# sem8700.net
KiCad netlist of a schematic drawn in Altium Designer
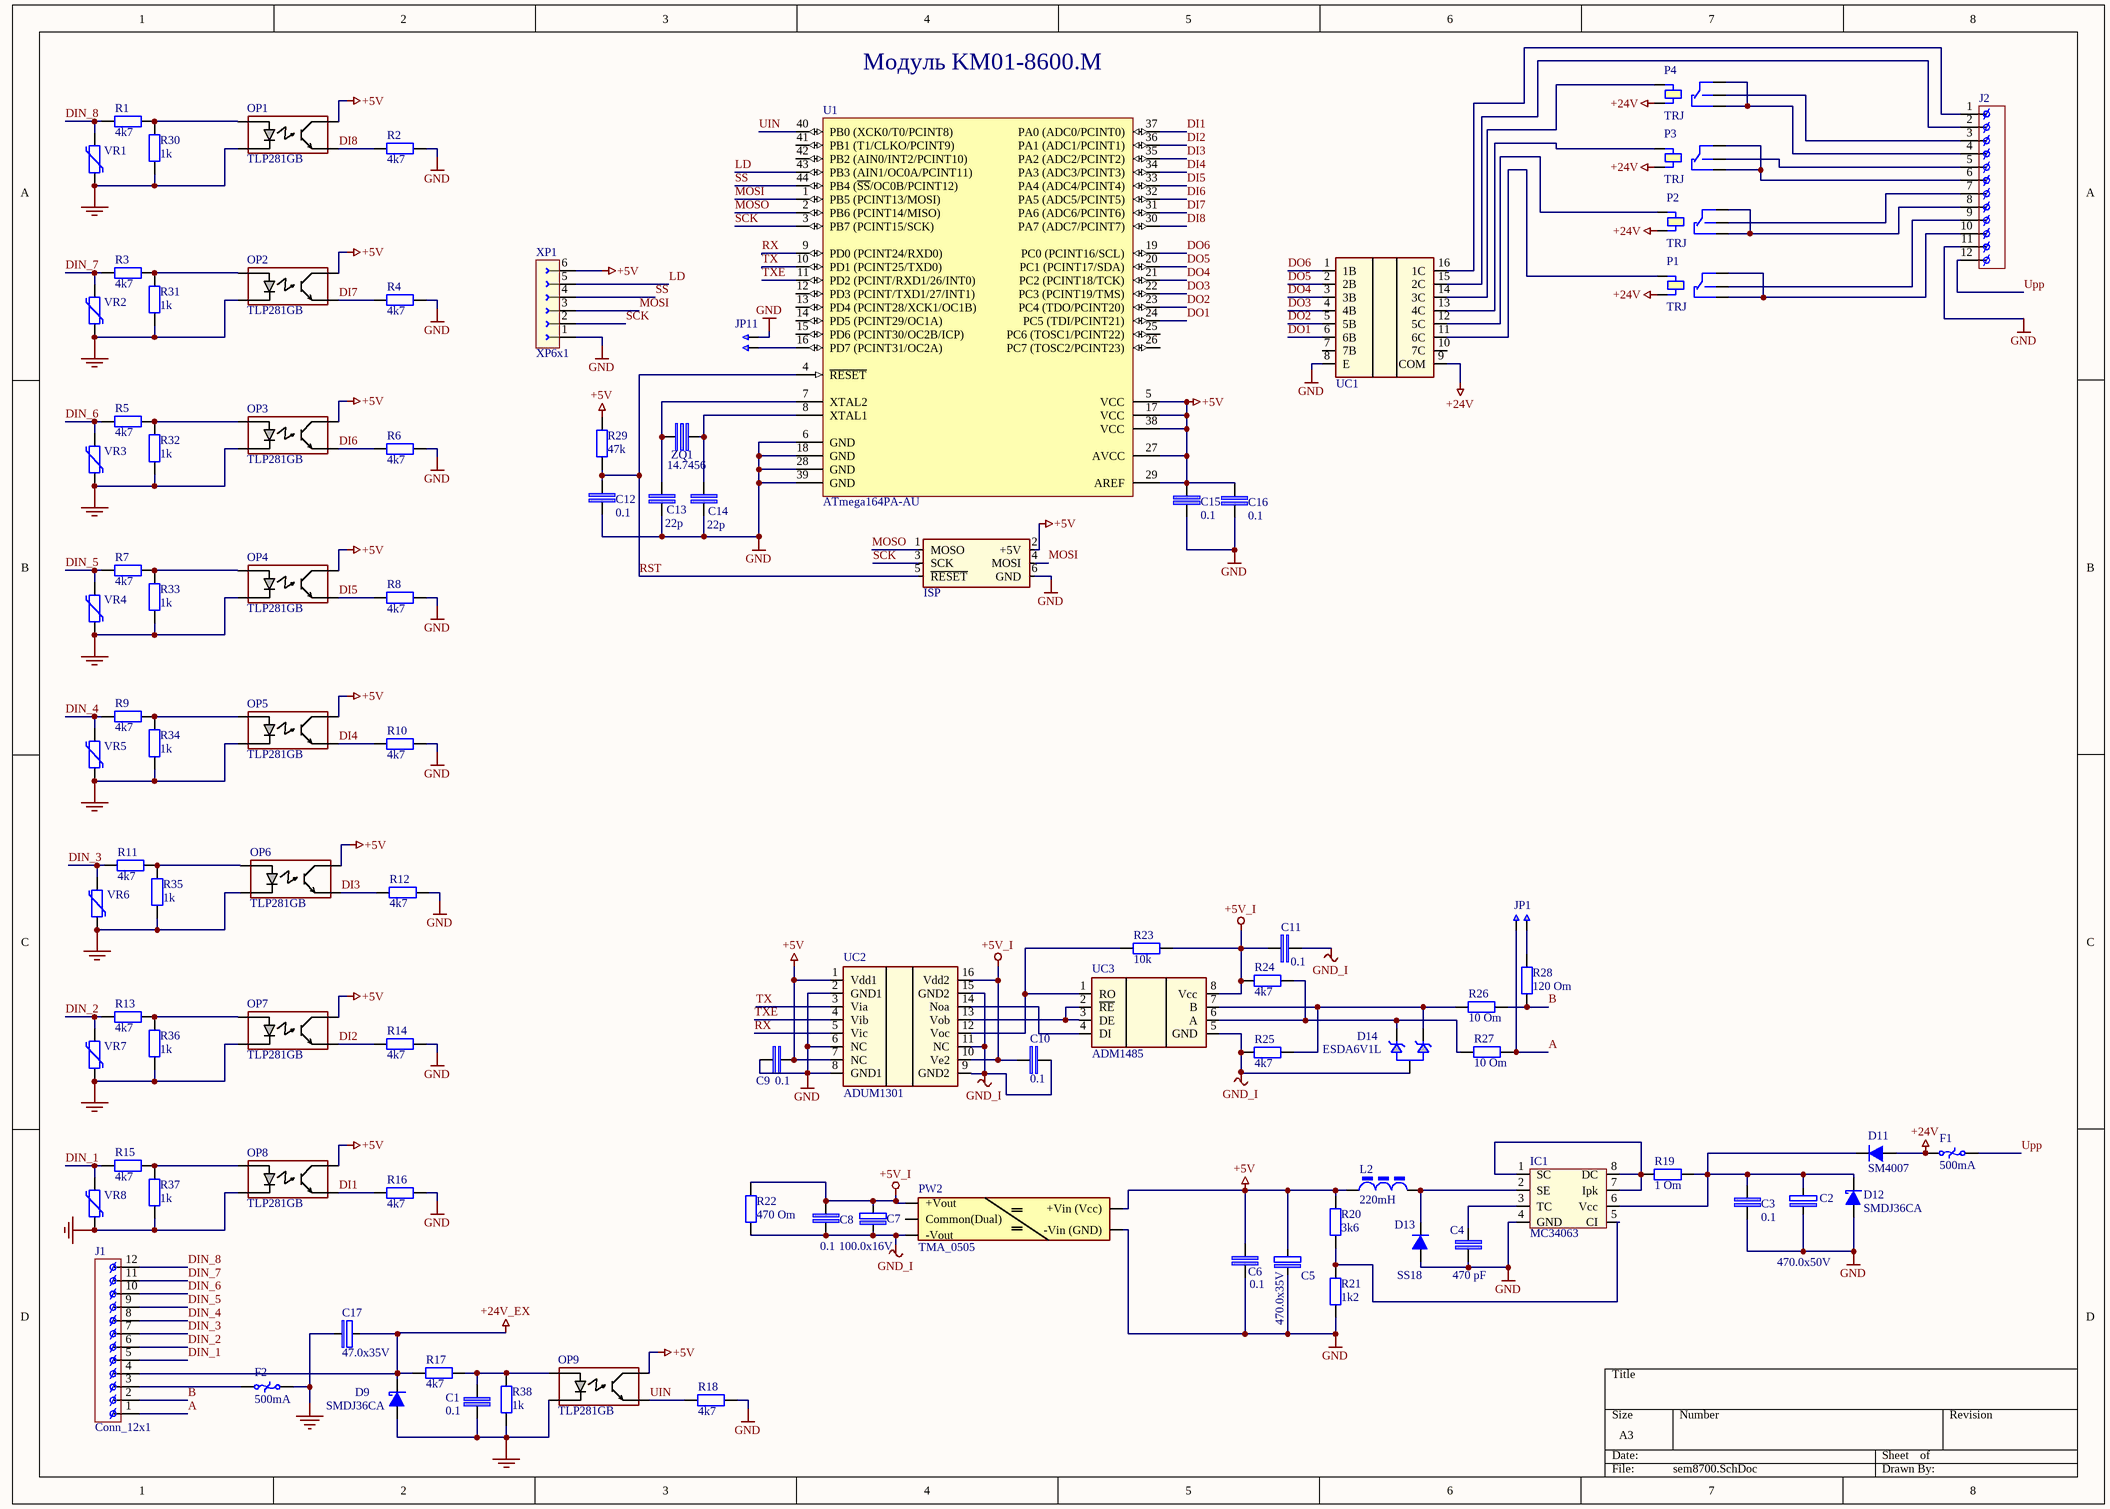
[diagram p0: sem8700.SchDoc]

(export (version "E")
  (design (tool "Eeschema 10.0.6"))
  (components
    (comp (ref "C1") (value "0.1") (footprint "CAPC2113X13N_0805") (libsource (lib "Lib_my1") (part "cap_1")))
    (comp (ref "C2")
      (value "470.0x50V")
      (footprint "Cap_pol_13x25")
      (libsource (lib "Lib_my1") (part "Cap_pol1"))
    )
    (comp (ref "C3") (value "0.1") (footprint "CAPC2113X13N_0805") (libsource (lib "Lib_my1") (part "cap_1")))
    (comp (ref "C4")
      (value "470 pF")
      (footprint "CAPC2113X13N_0805")
      (libsource (lib "Lib_my1") (part "cap_1"))
    )
    (comp (ref "C5")
      (value "470.0x35V")
      (footprint "Cap_2(10x12.5)")
      (libsource (lib "Lib_my1") (part "Cap_pol2"))
    )
    (comp (ref "C6") (value "0.1") (footprint "CAPC2113X13N_0805") (libsource (lib "Lib_my1") (part "cap_1")))
    (comp (ref "C7") (value "100.0x16V") (footprint "Cap_4(5x10)") (libsource (lib "") (part "Cap_pol2_1")))
    (comp (ref "C8") (value "0.1") (footprint "CAPC2113X13N_0805") (libsource (lib "") (part "cap_1_1")))
    (comp (ref "C9") (value "0.1") (footprint "CAPC2113X13N_0805") (libsource (lib "") (part "cap_1_1")))
    (comp (ref "C10") (value "0.1") (footprint "CAPC2113X13N_0805") (libsource (lib "") (part "cap_1_2")))
    (comp (ref "C11") (value "0.1") (footprint "CAPC2113X13N_0805") (libsource (lib "") (part "cap_1_1")))
    (comp (ref "C12")
      (value "0.1")
      (footprint "CAPC2113X13N_0805")
      (libsource (lib "Lib_my1") (part "cap_1"))
    )
    (comp (ref "C13")
      (value "22p")
      (footprint "CAPC2113X13N_0805")
      (libsource (lib "Lib_my1") (part "cap_1"))
    )
    (comp (ref "C14")
      (value "22p")
      (footprint "CAPC2113X13N_0805")
      (libsource (lib "Lib_my1") (part "cap_1"))
    )
    (comp (ref "C15")
      (value "0.1")
      (footprint "CAPC2113X13N_0805")
      (libsource (lib "Lib_my1") (part "cap_1"))
    )
    (comp (ref "C16")
      (value "0.1")
      (footprint "CAPC2113X13N_0805")
      (libsource (lib "Lib_my1") (part "cap_1"))
    )
    (comp (ref "C17")
      (value "47.0x35V")
      (footprint "Cap_4(5x10)")
      (libsource (lib "Lib_my1") (part "Cap_pol2"))
    )
    (comp (ref "D9") (value "SMDJ36CA") (footprint "SMB_1") (libsource (lib "Lib_my1") (part "Diodes_SMB")))
    (comp (ref "D11")
      (value "SM4007")
      (footprint "DIOD_SM1")
      (libsource (lib "Lib_my1") (part "Diodes_4007"))
    )
    (comp (ref "D12") (value "SMDJ36CA") (footprint "SMB_1") (libsource (lib "Lib_my1") (part "Diodes_SMB")))
    (comp (ref "D13") (value "SS18") (footprint "DIOD_SMA") (libsource (lib "Lib_my1") (part "Diod_30BQ100")))
    (comp (ref "D14")
      (value "ESDA6V1L")
      (footprint "SOT23_diod_ESDA")
      (libsource (lib "Lib_my1") (part "Diod_ESDA"))
    )
    (comp (ref "F1") (value "500mA") (footprint "Fuse_termo") (libsource (lib "Lib_my1") (part "Fuse_term")))
    (comp (ref "F2") (value "500mA") (footprint "Fuse_termo") (libsource (lib "Lib_my1") (part "Fuse_term")))
    (comp (ref "IC1")
      (value "MC34063")
      (footprint "SOIC_SO-8")
      (libsource (lib "Lib_my1") (part "MC34063_1"))
    )
    (comp (ref "ISP") (value "ISP") (footprint "ISP_1") (libsource (lib "Lib_my1") (part "ISP_1")))
    (comp (ref "J1") (value "Conn_12x1") (footprint "conn12_2") (libsource (lib "") (part "Conn_12x1_1")))
    (comp (ref "J2")
      (value "Conn_12x1")
      (footprint "conn12_2")
      (libsource (lib "Lib_my1") (part "Conn_12x1"))
    )
    (comp (ref "JP1") (value "jamper") (footprint "JP_2_2.5") (libsource (lib "Lib_my1") (part "JP_2x2.5")))
    (comp (ref "JP11") (value "jamper") (footprint "JP_2_2.5") (libsource (lib "Lib_my1") (part "JP_2x2.5")))
    (comp (ref "L2") (value "220mH") (footprint "Dr_1") (libsource (lib "Lib_my1") (part "Dr_1")))
    (comp (ref "OP1")
      (value "TLP281GB")
      (footprint "SOIC127_TPL")
      (libsource (lib "Lib_my1") (part "opto_TLP"))
    )
    (comp (ref "OP2")
      (value "TLP281GB")
      (footprint "SOIC127_TPL")
      (libsource (lib "Lib_my1") (part "opto_TLP"))
    )
    (comp (ref "OP3")
      (value "TLP281GB")
      (footprint "SOIC127_TPL")
      (libsource (lib "Lib_my1") (part "opto_TLP"))
    )
    (comp (ref "OP4")
      (value "TLP281GB")
      (footprint "SOIC127_TPL")
      (libsource (lib "Lib_my1") (part "opto_TLP"))
    )
    (comp (ref "OP5")
      (value "TLP281GB")
      (footprint "SOIC127_TPL")
      (libsource (lib "Lib_my1") (part "opto_TLP"))
    )
    (comp (ref "OP6")
      (value "TLP281GB")
      (footprint "SOIC127_TPL")
      (libsource (lib "Lib_my1") (part "opto_TLP"))
    )
    (comp (ref "OP7")
      (value "TLP281GB")
      (footprint "SOIC127_TPL")
      (libsource (lib "Lib_my1") (part "opto_TLP"))
    )
    (comp (ref "OP8")
      (value "TLP281GB")
      (footprint "SOIC127_TPL")
      (libsource (lib "Lib_my1") (part "opto_TLP"))
    )
    (comp (ref "OP9")
      (value "TLP281GB")
      (footprint "SOIC127_TPL")
      (libsource (lib "Lib_my1") (part "opto_TLP"))
    )
    (comp (ref "P1") (value "TRJ") (footprint "PCB_RELE_TRJ1") (libsource (lib "Lib_my1") (part "Rele_TRJ")))
    (comp (ref "P2") (value "TRJ") (footprint "PCB_RELE_TRJ1") (libsource (lib "Lib_my1") (part "Rele_TRJ")))
    (comp (ref "P3") (value "TRJ") (footprint "PCB_RELE_TRJ1") (libsource (lib "Lib_my1") (part "Rele_TRJ")))
    (comp (ref "P4") (value "TRJ") (footprint "PCB_RELE_TRJ1") (libsource (lib "Lib_my1") (part "Rele_TRJ")))
    (comp (ref "PW2")
      (value "TMA_0505")
      (footprint "TMA_1W_new")
      (libsource (lib "Lib_my1") (part "TRACO_PW1"))
    )
    (comp (ref "R1") (value "4k7") (footprint "RES_1206") (libsource (lib "") (part "rez_1_1")))
    (comp (ref "R2") (value "4k7") (footprint "RESC2113X0805N") (libsource (lib "") (part "rez_1_1")))
    (comp (ref "R3") (value "4k7") (footprint "RES_1206") (libsource (lib "") (part "rez_1_1")))
    (comp (ref "R4") (value "4k7") (footprint "RESC2113X0805N") (libsource (lib "") (part "rez_1_1")))
    (comp (ref "R5") (value "4k7") (footprint "RES_1206") (libsource (lib "") (part "rez_1_1")))
    (comp (ref "R6") (value "4k7") (footprint "RESC2113X0805N") (libsource (lib "") (part "rez_1_1")))
    (comp (ref "R7") (value "4k7") (footprint "RES_1206") (libsource (lib "") (part "rez_1_1")))
    (comp (ref "R8") (value "4k7") (footprint "RESC2113X0805N") (libsource (lib "") (part "rez_1_1")))
    (comp (ref "R9") (value "4k7") (footprint "RES_1206") (libsource (lib "") (part "rez_1_1")))
    (comp (ref "R10") (value "4k7") (footprint "RESC2113X0805N") (libsource (lib "") (part "rez_1_1")))
    (comp (ref "R11") (value "4k7") (footprint "RES_1206") (libsource (lib "") (part "rez_1_1")))
    (comp (ref "R12") (value "4k7") (footprint "RESC2113X0805N") (libsource (lib "") (part "rez_1_1")))
    (comp (ref "R13") (value "4k7") (footprint "RES_1206") (libsource (lib "") (part "rez_1_1")))
    (comp (ref "R14") (value "4k7") (footprint "RESC2113X0805N") (libsource (lib "") (part "rez_1_1")))
    (comp (ref "R15") (value "4k7") (footprint "RES_1206") (libsource (lib "") (part "rez_1_1")))
    (comp (ref "R16") (value "4k7") (footprint "RESC2113X0805N") (libsource (lib "") (part "rez_1_1")))
    (comp (ref "R17") (value "4k7") (footprint "RES_1206") (libsource (lib "") (part "rez_1_1")))
    (comp (ref "R18") (value "4k7") (footprint "RESC2113X0805N") (libsource (lib "") (part "rez_1_1")))
    (comp (ref "R19") (value "1 Om") (footprint "RES_1206") (libsource (lib "") (part "rez_1_1")))
    (comp (ref "R20") (value "3k6") (footprint "RESC2113X0805N") (libsource (lib "Lib_my1") (part "rez_1")))
    (comp (ref "R21") (value "1k2") (footprint "RESC2113X0805N") (libsource (lib "Lib_my1") (part "rez_1")))
    (comp (ref "R22") (value "470 Om") (footprint "RES_1206") (libsource (lib "") (part "rez_1_3")))
    (comp (ref "R23") (value "10k") (footprint "RESC2113X0805N") (libsource (lib "") (part "rez_1_3")))
    (comp (ref "R24") (value "4k7") (footprint "RESC2113X0805N") (libsource (lib "") (part "rez_1_3")))
    (comp (ref "R25") (value "4k7") (footprint "RESC2113X0805N") (libsource (lib "") (part "rez_1_3")))
    (comp (ref "R26") (value "10 Om") (footprint "RESC2113X0805N") (libsource (lib "") (part "rez_1_3")))
    (comp (ref "R27") (value "10 Om") (footprint "RESC2113X0805N") (libsource (lib "") (part "rez_1_3")))
    (comp (ref "R28") (value "120 Om") (footprint "RES_1206") (libsource (lib "Lib_my1") (part "rez_1")))
    (comp (ref "R29") (value "47k") (footprint "RESC2113X0805N") (libsource (lib "Lib_my1") (part "rez_1")))
    (comp (ref "R30") (value "1k") (footprint "RESC2113X0805N") (libsource (lib "") (part "rez_1_2")))
    (comp (ref "R31") (value "1k") (footprint "RESC2113X0805N") (libsource (lib "Lib_my1") (part "rez_1")))
    (comp (ref "R32") (value "1k") (footprint "RESC2113X0805N") (libsource (lib "Lib_my1") (part "rez_1")))
    (comp (ref "R33") (value "1k") (footprint "RESC2113X0805N") (libsource (lib "Lib_my1") (part "rez_1")))
    (comp (ref "R34") (value "1k") (footprint "RESC2113X0805N") (libsource (lib "Lib_my1") (part "rez_1")))
    (comp (ref "R35") (value "1k") (footprint "RESC2113X0805N") (libsource (lib "Lib_my1") (part "rez_1")))
    (comp (ref "R36") (value "1k") (footprint "RESC2113X0805N") (libsource (lib "Lib_my1") (part "rez_1")))
    (comp (ref "R37") (value "1k") (footprint "RESC2113X0805N") (libsource (lib "Lib_my1") (part "rez_1")))
    (comp (ref "R38") (value "1k") (footprint "RESC2113X0805N") (libsource (lib "Lib_my1") (part "rez_1")))
    (comp (ref "U1")
      (value "ATmega164PA-AU")
      (footprint "44A_N")
      (fields (field (name "PUBLISHER") "Altium Limited"))
      (libsource (lib "Atmel Microcontroller 8-Bit megaAVR") (part "ATmega164PA-AU"))
    )
    (comp (ref "UC1") (value "ULN2003A") (footprint "PDIP16_1") (libsource (lib "Lib_my1") (part "ULN2003A")))
    (comp (ref "UC2")
      (value "ADUM1301")
      (footprint "SOIC127P1030X265-16N_SOIC_W")
      (libsource (lib "Lib_my1") (part "ADUM1301"))
    )
    (comp (ref "UC3")
      (value "ADM1485")
      (footprint "SOIC127P600X175-8N_SOIC_SO8")
      (libsource (lib "Lib_my1") (part "ADM485"))
    )
    (comp (ref "VR1") (value "CN1206K25G") (footprint "var1206") (libsource (lib "") (part "var_smd1_1")))
    (comp (ref "VR2")
      (value "CN1206K25G")
      (footprint "var1206")
      (libsource (lib "Lib_my1") (part "var_smd1"))
    )
    (comp (ref "VR3")
      (value "CN1206K25G")
      (footprint "var1206")
      (libsource (lib "Lib_my1") (part "var_smd1"))
    )
    (comp (ref "VR4")
      (value "CN1206K25G")
      (footprint "var1206")
      (libsource (lib "Lib_my1") (part "var_smd1"))
    )
    (comp (ref "VR5")
      (value "CN1206K25G")
      (footprint "var1206")
      (libsource (lib "Lib_my1") (part "var_smd1"))
    )
    (comp (ref "VR6")
      (value "CN1206K25G")
      (footprint "var1206")
      (libsource (lib "Lib_my1") (part "var_smd1"))
    )
    (comp (ref "VR7")
      (value "CN1206K25G")
      (footprint "var1206")
      (libsource (lib "Lib_my1") (part "var_smd1"))
    )
    (comp (ref "VR8")
      (value "CN1206K25G")
      (footprint "var1206")
      (libsource (lib "Lib_my1") (part "var_smd1"))
    )
    (comp (ref "XP1") (value "XP6x1") (footprint "CONN_WF-6") (libsource (lib "Lib_my1") (part "Connect6_1")))
    (comp (ref "ZQ1") (value "14.7456") (footprint "ZQ_1") (libsource (lib "Lib_my1") (part "ZQ_1")))
  )
  (nets
    (net (code "1") (name "+5V") (class "Default")
      (node (ref "C15") (pin "1") (pinfunction "1_1") (pintype "passive"))
      (node (ref "C16") (pin "1") (pinfunction "1_1") (pintype "passive"))
      (node (ref "C5") (pin "1") (pinfunction "1_1") (pintype "passive"))
      (node (ref "C6") (pin "1") (pinfunction "1_1") (pintype "passive"))
      (node (ref "C9") (pin "1") (pinfunction "1_1") (pintype "passive"))
      (node (ref "ISP") (pin "2") (pinfunction "+5V_2") (pintype "passive"))
      (node (ref "L2") (pin "2") (pinfunction "2_2") (pintype "passive"))
      (node (ref "OP1") (pin "4") (pinfunction "4_4") (pintype "passive"))
      (node (ref "OP2") (pin "4") (pinfunction "4_4") (pintype "passive"))
      (node (ref "OP3") (pin "4") (pinfunction "4_4") (pintype "passive"))
      (node (ref "OP4") (pin "4") (pinfunction "4_4") (pintype "passive"))
      (node (ref "OP5") (pin "4") (pinfunction "4_4") (pintype "passive"))
      (node (ref "OP6") (pin "4") (pinfunction "4_4") (pintype "passive"))
      (node (ref "OP7") (pin "4") (pinfunction "4_4") (pintype "passive"))
      (node (ref "OP8") (pin "4") (pinfunction "4_4") (pintype "passive"))
      (node (ref "OP9") (pin "4") (pinfunction "4_4") (pintype "passive"))
      (node (ref "PW2") (pin "1") (pinfunction "+Vin_(Vcc)_1") (pintype "passive"))
      (node (ref "R20") (pin "2") (pinfunction "2_2") (pintype "passive"))
      (node (ref "R29") (pin "2") (pinfunction "2_2") (pintype "passive"))
      (node (ref "U1") (pin "17") (pinfunction "VCC_17") (pintype "power_in"))
      (node (ref "U1") (pin "27") (pinfunction "AVCC_27") (pintype "power_in"))
      (node (ref "U1") (pin "29") (pinfunction "AREF_29") (pintype "power_in"))
      (node (ref "U1") (pin "38") (pinfunction "VCC_38") (pintype "power_in"))
      (node (ref "U1") (pin "5") (pinfunction "VCC_5") (pintype "power_in"))
      (node (ref "UC2") (pin "1") (pinfunction "Vdd1_1") (pintype "passive"))
      (node (ref "UC2") (pin "7") (pinfunction "NC_7") (pintype "passive"))
      (node (ref "XP1") (pin "6") (pinfunction "6_6") (pintype "passive"))
    )
    (net (code "2") (name "+5V_I") (class "Default")
      (node (ref "C10") (pin "1") (pinfunction "1_1") (pintype "passive"))
      (node (ref "C11") (pin "2") (pinfunction "2_2") (pintype "passive"))
      (node (ref "C7") (pin "1") (pinfunction "1_1") (pintype "passive"))
      (node (ref "C8") (pin "1") (pinfunction "1_1") (pintype "passive"))
      (node (ref "PW2") (pin "5") (pinfunction "+Vout_5") (pintype "passive"))
      (node (ref "R22") (pin "1") (pinfunction "1_1") (pintype "passive"))
      (node (ref "R23") (pin "1") (pinfunction "1_1") (pintype "passive"))
      (node (ref "R24") (pin "2") (pinfunction "2_2") (pintype "passive"))
      (node (ref "UC2") (pin "10") (pinfunction "Ve2_10") (pintype "passive"))
      (node (ref "UC2") (pin "16") (pinfunction "Vdd2_16") (pintype "passive"))
      (node (ref "UC3") (pin "8") (pinfunction "Vcc_8") (pintype "passive"))
    )
    (net (code "3") (name "+24V") (class "Default")
      (node (ref "D11") (pin "1") (pinfunction "1_1") (pintype "passive"))
      (node (ref "F1") (pin "1") (pinfunction "1_1") (pintype "passive"))
      (node (ref "P1") (pin "5") (pinfunction "5_5") (pintype "passive"))
      (node (ref "P2") (pin "5") (pinfunction "5_5") (pintype "passive"))
      (node (ref "P3") (pin "5") (pinfunction "5_5") (pintype "passive"))
      (node (ref "P4") (pin "5") (pinfunction "5_5") (pintype "passive"))
      (node (ref "UC1") (pin "9") (pinfunction "COM_9") (pintype "passive"))
    )
    (net (code "4") (name "+24V_EX") (class "Default")
      (node (ref "C17") (pin "1") (pinfunction "1_1") (pintype "passive"))
      (node (ref "D9") (pin "1") (pinfunction "1_1") (pintype "passive"))
      (node (ref "J1") (pin "4") (pinfunction "4_4") (pintype "passive"))
      (node (ref "R17") (pin "1") (pinfunction "1_1") (pintype "passive"))
    )
    (net (code "5") (name "/A") (class "Default")
      (node (ref "J1") (pin "1") (pinfunction "1_1") (pintype "passive"))
      (node (ref "JP1") (pin "1") (pinfunction "1_1") (pintype "passive"))
      (node (ref "R27") (pin "1") (pinfunction "1_1") (pintype "passive"))
    )
    (net (code "6") (name "/B") (class "Default")
      (node (ref "J1") (pin "2") (pinfunction "2_2") (pintype "passive"))
      (node (ref "R26") (pin "1") (pinfunction "1_1") (pintype "passive"))
      (node (ref "R28") (pin "1") (pinfunction "1_1") (pintype "passive"))
    )
    (net (code "7") (name "/DI1") (class "Default")
      (node (ref "OP8") (pin "3") (pinfunction "3_3") (pintype "passive"))
      (node (ref "R16") (pin "1") (pinfunction "1_1") (pintype "passive"))
      (node (ref "U1") (pin "37") (pinfunction "PA0_(ADC0/PCINT0)_37") (pintype "bidirectional"))
    )
    (net (code "8") (name "/DI2") (class "Default")
      (node (ref "OP7") (pin "3") (pinfunction "3_3") (pintype "passive"))
      (node (ref "R14") (pin "1") (pinfunction "1_1") (pintype "passive"))
      (node (ref "U1") (pin "36") (pinfunction "PA1_(ADC1/PCINT1)_36") (pintype "bidirectional"))
    )
    (net (code "9") (name "/DI3") (class "Default")
      (node (ref "OP6") (pin "3") (pinfunction "3_3") (pintype "passive"))
      (node (ref "R12") (pin "1") (pinfunction "1_1") (pintype "passive"))
      (node (ref "U1") (pin "35") (pinfunction "PA2_(ADC2/PCINT2)_35") (pintype "bidirectional"))
    )
    (net (code "10") (name "/DI4") (class "Default")
      (node (ref "OP5") (pin "3") (pinfunction "3_3") (pintype "passive"))
      (node (ref "R10") (pin "1") (pinfunction "1_1") (pintype "passive"))
      (node (ref "U1") (pin "34") (pinfunction "PA3_(ADC3/PCINT3)_34") (pintype "bidirectional"))
    )
    (net (code "11") (name "/DI5") (class "Default")
      (node (ref "OP4") (pin "3") (pinfunction "3_3") (pintype "passive"))
      (node (ref "R8") (pin "1") (pinfunction "1_1") (pintype "passive"))
      (node (ref "U1") (pin "33") (pinfunction "PA4_(ADC4/PCINT4)_33") (pintype "bidirectional"))
    )
    (net (code "12") (name "/DI6") (class "Default")
      (node (ref "OP3") (pin "3") (pinfunction "3_3") (pintype "passive"))
      (node (ref "R6") (pin "1") (pinfunction "1_1") (pintype "passive"))
      (node (ref "U1") (pin "32") (pinfunction "PA5_(ADC5/PCINT5)_32") (pintype "bidirectional"))
    )
    (net (code "13") (name "/DI7") (class "Default")
      (node (ref "OP2") (pin "3") (pinfunction "3_3") (pintype "passive"))
      (node (ref "R4") (pin "1") (pinfunction "1_1") (pintype "passive"))
      (node (ref "U1") (pin "31") (pinfunction "PA6_(ADC6/PCINT6)_31") (pintype "bidirectional"))
    )
    (net (code "14") (name "/DI8") (class "Default")
      (node (ref "OP1") (pin "3") (pinfunction "3_3") (pintype "passive"))
      (node (ref "R2") (pin "1") (pinfunction "1_1") (pintype "passive"))
      (node (ref "U1") (pin "30") (pinfunction "PA7_(ADC7/PCINT7)_30") (pintype "bidirectional"))
    )
    (net (code "15") (name "/DIN_1") (class "Default")
      (node (ref "J1") (pin "5") (pinfunction "5_5") (pintype "passive"))
      (node (ref "R15") (pin "1") (pinfunction "1_1") (pintype "passive"))
      (node (ref "VR8") (pin "2") (pinfunction "2_2") (pintype "passive"))
    )
    (net (code "16") (name "/DIN_2") (class "Default")
      (node (ref "J1") (pin "6") (pinfunction "6_6") (pintype "passive"))
      (node (ref "R13") (pin "1") (pinfunction "1_1") (pintype "passive"))
      (node (ref "VR7") (pin "2") (pinfunction "2_2") (pintype "passive"))
    )
    (net (code "17") (name "/DIN_3") (class "Default")
      (node (ref "J1") (pin "7") (pinfunction "7_7") (pintype "passive"))
      (node (ref "R11") (pin "1") (pinfunction "1_1") (pintype "passive"))
      (node (ref "VR6") (pin "2") (pinfunction "2_2") (pintype "passive"))
    )
    (net (code "18") (name "/DIN_4") (class "Default")
      (node (ref "J1") (pin "8") (pinfunction "8_8") (pintype "passive"))
      (node (ref "R9") (pin "1") (pinfunction "1_1") (pintype "passive"))
      (node (ref "VR5") (pin "2") (pinfunction "2_2") (pintype "passive"))
    )
    (net (code "19") (name "/DIN_5") (class "Default")
      (node (ref "J1") (pin "9") (pinfunction "9_9") (pintype "passive"))
      (node (ref "R7") (pin "1") (pinfunction "1_1") (pintype "passive"))
      (node (ref "VR4") (pin "2") (pinfunction "2_2") (pintype "passive"))
    )
    (net (code "20") (name "/DIN_6") (class "Default")
      (node (ref "J1") (pin "10") (pinfunction "10_10") (pintype "passive"))
      (node (ref "R5") (pin "1") (pinfunction "1_1") (pintype "passive"))
      (node (ref "VR3") (pin "2") (pinfunction "2_2") (pintype "passive"))
    )
    (net (code "21") (name "/DIN_7") (class "Default")
      (node (ref "J1") (pin "11") (pinfunction "11_11") (pintype "passive"))
      (node (ref "R3") (pin "1") (pinfunction "1_1") (pintype "passive"))
      (node (ref "VR2") (pin "2") (pinfunction "2_2") (pintype "passive"))
    )
    (net (code "22") (name "/DIN_8") (class "Default")
      (node (ref "J1") (pin "12") (pinfunction "12_12") (pintype "passive"))
      (node (ref "R1") (pin "1") (pinfunction "1_1") (pintype "passive"))
      (node (ref "VR1") (pin "2") (pinfunction "2_2") (pintype "passive"))
    )
    (net (code "23") (name "/DO1") (class "Default")
      (node (ref "U1") (pin "24") (pinfunction "PC5_(TDI/PCINT21)_24") (pintype "bidirectional"))
      (node (ref "UC1") (pin "6") (pinfunction "6B_6") (pintype "passive"))
    )
    (net (code "24") (name "/DO2") (class "Default")
      (node (ref "U1") (pin "23") (pinfunction "PC4_(TDO/PCINT20)_23") (pintype "bidirectional"))
      (node (ref "UC1") (pin "5") (pinfunction "5B_5") (pintype "passive"))
    )
    (net (code "25") (name "/DO3") (class "Default")
      (node (ref "U1") (pin "22") (pinfunction "PC3_(PCINT19/TMS)_22") (pintype "bidirectional"))
      (node (ref "UC1") (pin "4") (pinfunction "4B_4") (pintype "passive"))
    )
    (net (code "26") (name "/DO4") (class "Default")
      (node (ref "U1") (pin "21") (pinfunction "PC2_(PCINT18/TCK)_21") (pintype "bidirectional"))
      (node (ref "UC1") (pin "3") (pinfunction "3B_3") (pintype "passive"))
    )
    (net (code "27") (name "/DO5") (class "Default")
      (node (ref "U1") (pin "20") (pinfunction "PC1_(PCINT17/SDA)_20") (pintype "bidirectional"))
      (node (ref "UC1") (pin "2") (pinfunction "2B_2") (pintype "passive"))
    )
    (net (code "28") (name "/DO6") (class "Default")
      (node (ref "U1") (pin "19") (pinfunction "PC0_(PCINT16/SCL)_19") (pintype "bidirectional"))
      (node (ref "UC1") (pin "1") (pinfunction "1B_1") (pintype "passive"))
    )
    (net (code "29") (name "/LD") (class "Default")
      (node (ref "U1") (pin "43") (pinfunction "PB3_(AIN1/OC0A/PCINT11)_43") (pintype "bidirectional"))
      (node (ref "XP1") (pin "5") (pinfunction "5_5") (pintype "passive"))
    )
    (net (code "30") (name "/MOSI") (class "Default")
      (node (ref "ISP") (pin "4") (pinfunction "MOSI_4") (pintype "passive"))
      (node (ref "U1") (pin "1") (pinfunction "PB5_(PCINT13/MOSI)_1") (pintype "bidirectional"))
      (node (ref "XP1") (pin "3") (pinfunction "3_3") (pintype "passive"))
    )
    (net (code "31") (name "/MOSO") (class "Default")
      (node (ref "ISP") (pin "1") (pinfunction "MOSO_1") (pintype "passive"))
      (node (ref "U1") (pin "2") (pinfunction "PB6_(PCINT14/MISO)_2") (pintype "bidirectional"))
    )
    (net (code "32") (name "/RST") (class "Default")
      (node (ref "C12") (pin "1") (pinfunction "1_1") (pintype "passive"))
      (node (ref "ISP") (pin "5") (pinfunction "~{RESET}_5") (pintype "passive"))
      (node (ref "R29") (pin "1") (pinfunction "1_1") (pintype "passive"))
      (node (ref "U1") (pin "4") (pinfunction "~{RESET}_4") (pintype "input"))
    )
    (net (code "33") (name "/RX") (class "Default")
      (node (ref "U1") (pin "9") (pinfunction "PD0_(PCINT24/RXD0)_9") (pintype "bidirectional"))
      (node (ref "UC2") (pin "5") (pinfunction "Vic_5") (pintype "passive"))
    )
    (net (code "34") (name "/SCK") (class "Default")
      (node (ref "ISP") (pin "3") (pinfunction "SCK_3") (pintype "passive"))
      (node (ref "U1") (pin "3") (pinfunction "PB7_(PCINT15/SCK)_3") (pintype "bidirectional"))
      (node (ref "XP1") (pin "2") (pinfunction "2_2") (pintype "passive"))
    )
    (net (code "35") (name "/SS") (class "Default")
      (node (ref "U1") (pin "44") (pinfunction "PB4_(~{SS}/OC0B/PCINT12)_44") (pintype "bidirectional"))
      (node (ref "XP1") (pin "4") (pinfunction "4_4") (pintype "passive"))
    )
    (net (code "36") (name "/TX") (class "Default")
      (node (ref "U1") (pin "10") (pinfunction "PD1_(PCINT25/TXD0)_10") (pintype "bidirectional"))
      (node (ref "UC2") (pin "3") (pinfunction "Via_3") (pintype "passive"))
    )
    (net (code "37") (name "/TXE") (class "Default")
      (node (ref "U1") (pin "11") (pinfunction "PD2_(PCINT/RXD1/26/INT0)_11") (pintype "bidirectional"))
      (node (ref "UC2") (pin "4") (pinfunction "Vib_4") (pintype "passive"))
    )
    (net (code "38") (name "/UIN") (class "Default")
      (node (ref "OP9") (pin "3") (pinfunction "3_3") (pintype "passive"))
      (node (ref "R18") (pin "1") (pinfunction "1_1") (pintype "passive"))
      (node (ref "U1") (pin "40") (pinfunction "PB0_(XCK0/T0/PCINT8)_40") (pintype "bidirectional"))
    )
    (net (code "39") (name "/Upp") (class "Default")
      (node (ref "F1") (pin "2") (pinfunction "2_2") (pintype "passive"))
      (node (ref "J2") (pin "12") (pinfunction "12_12") (pintype "passive"))
    )
    (net (code "40") (name "GND") (class "Default")
      (node (ref "C12") (pin "2") (pinfunction "2_2") (pintype "passive"))
      (node (ref "C13") (pin "2") (pinfunction "2_2") (pintype "passive"))
      (node (ref "C14") (pin "2") (pinfunction "2_2") (pintype "passive"))
      (node (ref "C15") (pin "2") (pinfunction "2_2") (pintype "passive"))
      (node (ref "C16") (pin "2") (pinfunction "2_2") (pintype "passive"))
      (node (ref "C2") (pin "2") (pinfunction "2_2") (pintype "passive"))
      (node (ref "C3") (pin "2") (pinfunction "2_2") (pintype "passive"))
      (node (ref "C4") (pin "2") (pinfunction "2_2") (pintype "passive"))
      (node (ref "C5") (pin "2") (pinfunction "2_2") (pintype "passive"))
      (node (ref "C6") (pin "2") (pinfunction "2_2") (pintype "passive"))
      (node (ref "C9") (pin "2") (pinfunction "2_2") (pintype "passive"))
      (node (ref "D12") (pin "2") (pinfunction "2_2") (pintype "passive"))
      (node (ref "D13") (pin "1") (pinfunction "1_1") (pintype "passive"))
      (node (ref "IC1") (pin "4") (pinfunction "GND_4") (pintype "passive"))
      (node (ref "ISP") (pin "6") (pinfunction "GND_6") (pintype "passive"))
      (node (ref "J2") (pin "11") (pinfunction "11_11") (pintype "passive"))
      (node (ref "JP11") (pin "2") (pinfunction "2_2") (pintype "passive"))
      (node (ref "PW2") (pin "2") (pinfunction "-Vin_(GND)_2") (pintype "passive"))
      (node (ref "R10") (pin "2") (pinfunction "2_2") (pintype "passive"))
      (node (ref "R12") (pin "2") (pinfunction "2_2") (pintype "passive"))
      (node (ref "R14") (pin "2") (pinfunction "2_2") (pintype "passive"))
      (node (ref "R16") (pin "2") (pinfunction "2_2") (pintype "passive"))
      (node (ref "R18") (pin "2") (pinfunction "2_2") (pintype "passive"))
      (node (ref "R2") (pin "2") (pinfunction "2_2") (pintype "passive"))
      (node (ref "R21") (pin "1") (pinfunction "1_1") (pintype "passive"))
      (node (ref "R4") (pin "2") (pinfunction "2_2") (pintype "passive"))
      (node (ref "R6") (pin "2") (pinfunction "2_2") (pintype "passive"))
      (node (ref "R8") (pin "2") (pinfunction "2_2") (pintype "passive"))
      (node (ref "U1") (pin "18") (pinfunction "GND_18") (pintype "power_in"))
      (node (ref "U1") (pin "28") (pinfunction "GND_28") (pintype "power_in"))
      (node (ref "U1") (pin "39") (pinfunction "GND_39") (pintype "power_in"))
      (node (ref "U1") (pin "6") (pinfunction "GND_6") (pintype "power_in"))
      (node (ref "UC1") (pin "8") (pinfunction "E_8") (pintype "passive"))
      (node (ref "UC2") (pin "2") (pinfunction "GND1_2") (pintype "passive"))
      (node (ref "UC2") (pin "6") (pinfunction "NC_6") (pintype "passive"))
      (node (ref "UC2") (pin "8") (pinfunction "GND1_8") (pintype "passive"))
      (node (ref "XP1") (pin "1") (pinfunction "1_1") (pintype "passive"))
    )
    (net (code "41") (name "GND_EX") (class "Default")
      (node (ref "C1") (pin "2") (pinfunction "2_2") (pintype "passive"))
      (node (ref "C17") (pin "2") (pinfunction "2_2") (pintype "passive"))
      (node (ref "D9") (pin "2") (pinfunction "2_2") (pintype "passive"))
      (node (ref "F2") (pin "2") (pinfunction "2_2") (pintype "passive"))
      (node (ref "OP1") (pin "2") (pinfunction "2_2") (pintype "passive"))
      (node (ref "OP2") (pin "2") (pinfunction "2_2") (pintype "passive"))
      (node (ref "OP3") (pin "2") (pinfunction "2_2") (pintype "passive"))
      (node (ref "OP4") (pin "2") (pinfunction "2_2") (pintype "passive"))
      (node (ref "OP5") (pin "2") (pinfunction "2_2") (pintype "passive"))
      (node (ref "OP6") (pin "2") (pinfunction "2_2") (pintype "passive"))
      (node (ref "OP7") (pin "2") (pinfunction "2_2") (pintype "passive"))
      (node (ref "OP8") (pin "2") (pinfunction "2_2") (pintype "passive"))
      (node (ref "OP9") (pin "2") (pinfunction "2_2") (pintype "passive"))
      (node (ref "R30") (pin "1") (pinfunction "1_1") (pintype "passive"))
      (node (ref "R31") (pin "1") (pinfunction "1_1") (pintype "passive"))
      (node (ref "R32") (pin "1") (pinfunction "1_1") (pintype "passive"))
      (node (ref "R33") (pin "1") (pinfunction "1_1") (pintype "passive"))
      (node (ref "R34") (pin "1") (pinfunction "1_1") (pintype "passive"))
      (node (ref "R35") (pin "1") (pinfunction "1_1") (pintype "passive"))
      (node (ref "R36") (pin "1") (pinfunction "1_1") (pintype "passive"))
      (node (ref "R37") (pin "1") (pinfunction "1_1") (pintype "passive"))
      (node (ref "R38") (pin "1") (pinfunction "1_1") (pintype "passive"))
      (node (ref "VR1") (pin "1") (pinfunction "1_1") (pintype "passive"))
      (node (ref "VR2") (pin "1") (pinfunction "1_1") (pintype "passive"))
      (node (ref "VR3") (pin "1") (pinfunction "1_1") (pintype "passive"))
      (node (ref "VR4") (pin "1") (pinfunction "1_1") (pintype "passive"))
      (node (ref "VR5") (pin "1") (pinfunction "1_1") (pintype "passive"))
      (node (ref "VR6") (pin "1") (pinfunction "1_1") (pintype "passive"))
      (node (ref "VR7") (pin "1") (pinfunction "1_1") (pintype "passive"))
      (node (ref "VR8") (pin "1") (pinfunction "1_1") (pintype "passive"))
    )
    (net (code "42") (name "GND_I") (class "Default")
      (node (ref "C10") (pin "2") (pinfunction "2_2") (pintype "passive"))
      (node (ref "C11") (pin "1") (pinfunction "1_1") (pintype "passive"))
      (node (ref "C7") (pin "2") (pinfunction "2_2") (pintype "passive"))
      (node (ref "C8") (pin "2") (pinfunction "2_2") (pintype "passive"))
      (node (ref "D14") (pin "3") (pinfunction "3_3") (pintype "passive"))
      (node (ref "PW2") (pin "3") (pinfunction "-Vout_3") (pintype "passive"))
      (node (ref "R22") (pin "2") (pinfunction "2_2") (pintype "passive"))
      (node (ref "R25") (pin "2") (pinfunction "2_2") (pintype "passive"))
      (node (ref "UC2") (pin "11") (pinfunction "NC_11") (pintype "passive"))
      (node (ref "UC2") (pin "15") (pinfunction "GND2_15") (pintype "passive"))
      (node (ref "UC2") (pin "9") (pinfunction "GND2_9") (pintype "passive"))
      (node (ref "UC3") (pin "5") (pinfunction "GND_5") (pintype "passive"))
    )
    (net (code "43") (name "Net-(C1-Pad1)") (class "Default")
      (node (ref "C1") (pin "1") (pinfunction "1_1") (pintype "passive"))
      (node (ref "OP9") (pin "1") (pinfunction "1_1") (pintype "passive"))
      (node (ref "R17") (pin "2") (pinfunction "2_2") (pintype "passive"))
      (node (ref "R38") (pin "2") (pinfunction "2_2") (pintype "passive"))
    )
    (net (code "44") (name "Net-(F2-Pad1)") (class "Default")
      (node (ref "F2") (pin "1") (pinfunction "1_1") (pintype "passive"))
      (node (ref "J1") (pin "3") (pinfunction "3_3") (pintype "passive"))
    )
    (net (code "45") (name "Net-(IC1-CI)") (class "Default")
      (node (ref "IC1") (pin "5") (pinfunction "CI_5") (pintype "passive"))
      (node (ref "R20") (pin "1") (pinfunction "1_1") (pintype "passive"))
      (node (ref "R21") (pin "2") (pinfunction "2_2") (pintype "passive"))
    )
    (net (code "46") (name "Net-(IC1-DC)") (class "Default")
      (node (ref "IC1") (pin "1") (pinfunction "SC_1") (pintype "passive"))
      (node (ref "IC1") (pin "7") (pinfunction "Ipk_7") (pintype "passive"))
      (node (ref "IC1") (pin "8") (pinfunction "DC_8") (pintype "passive"))
      (node (ref "R19") (pin "1") (pinfunction "1_1") (pintype "passive"))
    )
    (net (code "47") (name "Net-(IC1-SE)") (class "Default")
      (node (ref "D13") (pin "2") (pinfunction "2_2") (pintype "passive"))
      (node (ref "IC1") (pin "2") (pinfunction "SE_2") (pintype "passive"))
      (node (ref "L2") (pin "1") (pinfunction "1_1") (pintype "passive"))
    )
    (net (code "48") (name "Net-(IC1-TC)") (class "Default")
      (node (ref "C4") (pin "1") (pinfunction "1_1") (pintype "passive"))
      (node (ref "IC1") (pin "3") (pinfunction "TC_3") (pintype "passive"))
    )
    (net (code "49") (name "Net-(IC1-Vcc)") (class "Default")
      (node (ref "C2") (pin "1") (pinfunction "1_1") (pintype "passive"))
      (node (ref "C3") (pin "1") (pinfunction "1_1") (pintype "passive"))
      (node (ref "D11") (pin "2") (pinfunction "2_2") (pintype "passive"))
      (node (ref "D12") (pin "1") (pinfunction "1_1") (pintype "passive"))
      (node (ref "IC1") (pin "6") (pinfunction "Vcc_6") (pintype "passive"))
      (node (ref "R19") (pin "2") (pinfunction "2_2") (pintype "passive"))
    )
    (net (code "50") (name "Net-(J2-Pad3)") (class "Default")
      (node (ref "J2") (pin "3") (pinfunction "3_3") (pintype "passive"))
      (node (ref "P4") (pin "3") (pinfunction "3_3") (pintype "passive"))
    )
    (net (code "51") (name "Net-(J2-Pad4)") (class "Default")
      (node (ref "J2") (pin "4") (pinfunction "4_4") (pintype "passive"))
      (node (ref "P4") (pin "2") (pinfunction "2_2") (pintype "passive"))
      (node (ref "P4") (pin "4") (pinfunction "4_4") (pintype "passive"))
    )
    (net (code "52") (name "Net-(J2-Pad5)") (class "Default")
      (node (ref "J2") (pin "5") (pinfunction "5_5") (pintype "passive"))
      (node (ref "P3") (pin "3") (pinfunction "3_3") (pintype "passive"))
    )
    (net (code "53") (name "Net-(J2-Pad6)") (class "Default")
      (node (ref "J2") (pin "6") (pinfunction "6_6") (pintype "passive"))
      (node (ref "P3") (pin "2") (pinfunction "2_2") (pintype "passive"))
      (node (ref "P3") (pin "4") (pinfunction "4_4") (pintype "passive"))
    )
    (net (code "54") (name "Net-(J2-Pad7)") (class "Default")
      (node (ref "J2") (pin "7") (pinfunction "7_7") (pintype "passive"))
      (node (ref "P2") (pin "3") (pinfunction "3_3") (pintype "passive"))
    )
    (net (code "55") (name "Net-(J2-Pad8)") (class "Default")
      (node (ref "J2") (pin "8") (pinfunction "8_8") (pintype "passive"))
      (node (ref "P2") (pin "2") (pinfunction "2_2") (pintype "passive"))
      (node (ref "P2") (pin "4") (pinfunction "4_4") (pintype "passive"))
    )
    (net (code "56") (name "Net-(J2-Pad9)") (class "Default")
      (node (ref "J2") (pin "9") (pinfunction "9_9") (pintype "passive"))
      (node (ref "P1") (pin "3") (pinfunction "3_3") (pintype "passive"))
    )
    (net (code "57") (name "Net-(J2-Pad10)") (class "Default")
      (node (ref "J2") (pin "10") (pinfunction "10_10") (pintype "passive"))
      (node (ref "P1") (pin "2") (pinfunction "2_2") (pintype "passive"))
      (node (ref "P1") (pin "4") (pinfunction "4_4") (pintype "passive"))
    )
    (net (code "58") (name "Net-(JP1-Pad2)") (class "Default")
      (node (ref "JP1") (pin "2") (pinfunction "2_2") (pintype "passive"))
      (node (ref "R28") (pin "2") (pinfunction "2_2") (pintype "passive"))
    )
    (net (code "59") (name "Net-(OP1-Pad1)") (class "Default")
      (node (ref "OP1") (pin "1") (pinfunction "1_1") (pintype "passive"))
      (node (ref "R1") (pin "2") (pinfunction "2_2") (pintype "passive"))
      (node (ref "R30") (pin "2") (pinfunction "2_2") (pintype "passive"))
    )
    (net (code "60") (name "Net-(OP2-Pad1)") (class "Default")
      (node (ref "OP2") (pin "1") (pinfunction "1_1") (pintype "passive"))
      (node (ref "R3") (pin "2") (pinfunction "2_2") (pintype "passive"))
      (node (ref "R31") (pin "2") (pinfunction "2_2") (pintype "passive"))
    )
    (net (code "61") (name "Net-(OP3-Pad1)") (class "Default")
      (node (ref "OP3") (pin "1") (pinfunction "1_1") (pintype "passive"))
      (node (ref "R32") (pin "2") (pinfunction "2_2") (pintype "passive"))
      (node (ref "R5") (pin "2") (pinfunction "2_2") (pintype "passive"))
    )
    (net (code "62") (name "Net-(OP4-Pad1)") (class "Default")
      (node (ref "OP4") (pin "1") (pinfunction "1_1") (pintype "passive"))
      (node (ref "R33") (pin "2") (pinfunction "2_2") (pintype "passive"))
      (node (ref "R7") (pin "2") (pinfunction "2_2") (pintype "passive"))
    )
    (net (code "63") (name "Net-(OP5-Pad1)") (class "Default")
      (node (ref "OP5") (pin "1") (pinfunction "1_1") (pintype "passive"))
      (node (ref "R34") (pin "2") (pinfunction "2_2") (pintype "passive"))
      (node (ref "R9") (pin "2") (pinfunction "2_2") (pintype "passive"))
    )
    (net (code "64") (name "Net-(OP6-Pad1)") (class "Default")
      (node (ref "OP6") (pin "1") (pinfunction "1_1") (pintype "passive"))
      (node (ref "R11") (pin "2") (pinfunction "2_2") (pintype "passive"))
      (node (ref "R35") (pin "2") (pinfunction "2_2") (pintype "passive"))
    )
    (net (code "65") (name "Net-(OP7-Pad1)") (class "Default")
      (node (ref "OP7") (pin "1") (pinfunction "1_1") (pintype "passive"))
      (node (ref "R13") (pin "2") (pinfunction "2_2") (pintype "passive"))
      (node (ref "R36") (pin "2") (pinfunction "2_2") (pintype "passive"))
    )
    (net (code "66") (name "Net-(OP8-Pad1)") (class "Default")
      (node (ref "OP8") (pin "1") (pinfunction "1_1") (pintype "passive"))
      (node (ref "R15") (pin "2") (pinfunction "2_2") (pintype "passive"))
      (node (ref "R37") (pin "2") (pinfunction "2_2") (pintype "passive"))
    )
    (net (code "67") (name "Net-(U1-PD7_(PCINT31{slash}OC2A))") (class "Default")
      (node (ref "JP11") (pin "1") (pinfunction "1_1") (pintype "passive"))
      (node (ref "U1") (pin "16") (pinfunction "PD7_(PCINT31/OC2A)_16") (pintype "bidirectional"))
    )
    (net (code "68") (name "Net-(U1-XTAL1)") (class "Default")
      (node (ref "C14") (pin "1") (pinfunction "1_1") (pintype "passive"))
      (node (ref "U1") (pin "8") (pinfunction "XTAL1_8") (pintype "passive"))
      (node (ref "ZQ1") (pin "2") (pinfunction "2_2") (pintype "passive"))
    )
    (net (code "69") (name "Net-(U1-XTAL2)") (class "Default")
      (node (ref "C13") (pin "1") (pinfunction "1_1") (pintype "passive"))
      (node (ref "U1") (pin "7") (pinfunction "XTAL2_7") (pintype "passive"))
      (node (ref "ZQ1") (pin "1") (pinfunction "1_1") (pintype "passive"))
    )
    (net (code "70") (name "Net-(UC1-1C)") (class "Default")
      (node (ref "J2") (pin "1") (pinfunction "1_1") (pintype "passive"))
      (node (ref "UC1") (pin "16") (pinfunction "1C_16") (pintype "passive"))
    )
    (net (code "71") (name "Net-(UC1-2C)") (class "Default")
      (node (ref "J2") (pin "2") (pinfunction "2_2") (pintype "passive"))
      (node (ref "UC1") (pin "15") (pinfunction "2C_15") (pintype "passive"))
    )
    (net (code "72") (name "Net-(UC1-3C)") (class "Default")
      (node (ref "P4") (pin "1") (pinfunction "1_1") (pintype "passive"))
      (node (ref "UC1") (pin "14") (pinfunction "3C_14") (pintype "passive"))
    )
    (net (code "73") (name "Net-(UC1-4C)") (class "Default")
      (node (ref "P3") (pin "1") (pinfunction "1_1") (pintype "passive"))
      (node (ref "UC1") (pin "13") (pinfunction "4C_13") (pintype "passive"))
    )
    (net (code "74") (name "Net-(UC1-5C)") (class "Default")
      (node (ref "P2") (pin "1") (pinfunction "1_1") (pintype "passive"))
      (node (ref "UC1") (pin "12") (pinfunction "5C_12") (pintype "passive"))
    )
    (net (code "75") (name "Net-(UC1-6C)") (class "Default")
      (node (ref "P1") (pin "1") (pinfunction "1_1") (pintype "passive"))
      (node (ref "UC1") (pin "11") (pinfunction "6C_11") (pintype "passive"))
    )
    (net (code "76") (name "Net-(UC2-Noa)") (class "Default")
      (node (ref "UC2") (pin "14") (pinfunction "Noa_14") (pintype "passive"))
      (node (ref "UC3") (pin "4") (pinfunction "DI_4") (pintype "passive"))
    )
    (net (code "77") (name "Net-(UC2-Vob)") (class "Default")
      (node (ref "UC2") (pin "13") (pinfunction "Vob_13") (pintype "passive"))
      (node (ref "UC3") (pin "2") (pinfunction "~{RE}_2") (pintype "passive"))
      (node (ref "UC3") (pin "3") (pinfunction "DE_3") (pintype "passive"))
    )
    (net (code "78") (name "Net-(UC2-Voc)") (class "Default")
      (node (ref "R23") (pin "2") (pinfunction "2_2") (pintype "passive"))
      (node (ref "UC2") (pin "12") (pinfunction "Voc_12") (pintype "passive"))
      (node (ref "UC3") (pin "1") (pinfunction "RO_1") (pintype "passive"))
    )
    (net (code "79") (name "Net-(UC3-A)") (class "Default")
      (node (ref "D14") (pin "2") (pinfunction "2_2") (pintype "passive"))
      (node (ref "R24") (pin "1") (pinfunction "1_1") (pintype "passive"))
      (node (ref "R27") (pin "2") (pinfunction "2_2") (pintype "passive"))
      (node (ref "UC3") (pin "6") (pinfunction "A_6") (pintype "passive"))
    )
    (net (code "80") (name "Net-(UC3-B)") (class "Default")
      (node (ref "D14") (pin "1") (pinfunction "1_1") (pintype "passive"))
      (node (ref "R25") (pin "1") (pinfunction "1_1") (pintype "passive"))
      (node (ref "R26") (pin "2") (pinfunction "2_2") (pintype "passive"))
      (node (ref "UC3") (pin "7") (pinfunction "B_7") (pintype "passive"))
    )
    (net (code "81") (name "unconnected-(PW2-Common(Dual)-Pad4)") (class "Default")
      (node (ref "PW2") (pin "4") (pinfunction "Common(Dual)_4") (pintype "passive"))
    )
    (net (code "82") (name "unconnected-(U1-PB1_(T1{slash}CLKO{slash}PCINT9)-Pad41)") (class "Default")
      (node (ref "U1") (pin "41") (pinfunction "PB1_(T1/CLKO/PCINT9)_41") (pintype "bidirectional"))
    )
    (net (code "83") (name "unconnected-(U1-PB2_(AIN0{slash}INT2{slash}PCINT10)-Pad42)") (class "Default")
      (node (ref "U1") (pin "42") (pinfunction "PB2_(AIN0/INT2/PCINT10)_42") (pintype "bidirectional"))
    )
    (net (code "84") (name "unconnected-(U1-PC6_(TOSC1{slash}PCINT22)-Pad25)") (class "Default")
      (node (ref "U1") (pin "25") (pinfunction "PC6_(TOSC1/PCINT22)_25") (pintype "bidirectional"))
    )
    (net (code "85") (name "unconnected-(U1-PC7_(TOSC2{slash}PCINT23)-Pad26)") (class "Default")
      (node (ref "U1") (pin "26") (pinfunction "PC7_(TOSC2/PCINT23)_26") (pintype "bidirectional"))
    )
    (net (code "86") (name "unconnected-(U1-PD3_(PCINT{slash}TXD1{slash}27{slash}INT1)-Pad12)") (class "Default")
      (node (ref "U1") (pin "12") (pinfunction "PD3_(PCINT/TXD1/27/INT1)_12") (pintype "bidirectional"))
    )
    (net (code "87") (name "unconnected-(U1-PD4_(PCINT28{slash}XCK1{slash}OC1B)-Pad13)") (class "Default")
      (node (ref "U1") (pin "13") (pinfunction "PD4_(PCINT28/XCK1/OC1B)_13") (pintype "bidirectional"))
    )
    (net (code "88") (name "unconnected-(U1-PD5_(PCINT29{slash}OC1A)-Pad14)") (class "Default")
      (node (ref "U1") (pin "14") (pinfunction "PD5_(PCINT29/OC1A)_14") (pintype "bidirectional"))
    )
    (net (code "89") (name "unconnected-(U1-PD6_(PCINT30{slash}OC2B{slash}ICP)-Pad15)") (class "Default")
      (node (ref "U1") (pin "15") (pinfunction "PD6_(PCINT30/OC2B/ICP)_15") (pintype "bidirectional"))
    )
    (net (code "90") (name "unconnected-(UC1-7B-Pad7)") (class "Default")
      (node (ref "UC1") (pin "7") (pinfunction "7B_7") (pintype "passive"))
    )
    (net (code "91") (name "unconnected-(UC1-7C-Pad10)") (class "Default")
      (node (ref "UC1") (pin "10") (pinfunction "7C_10") (pintype "passive"))
    )
  )
)
